# MagBase.net
KiCad netlist of a schematic drawn in EAGLE
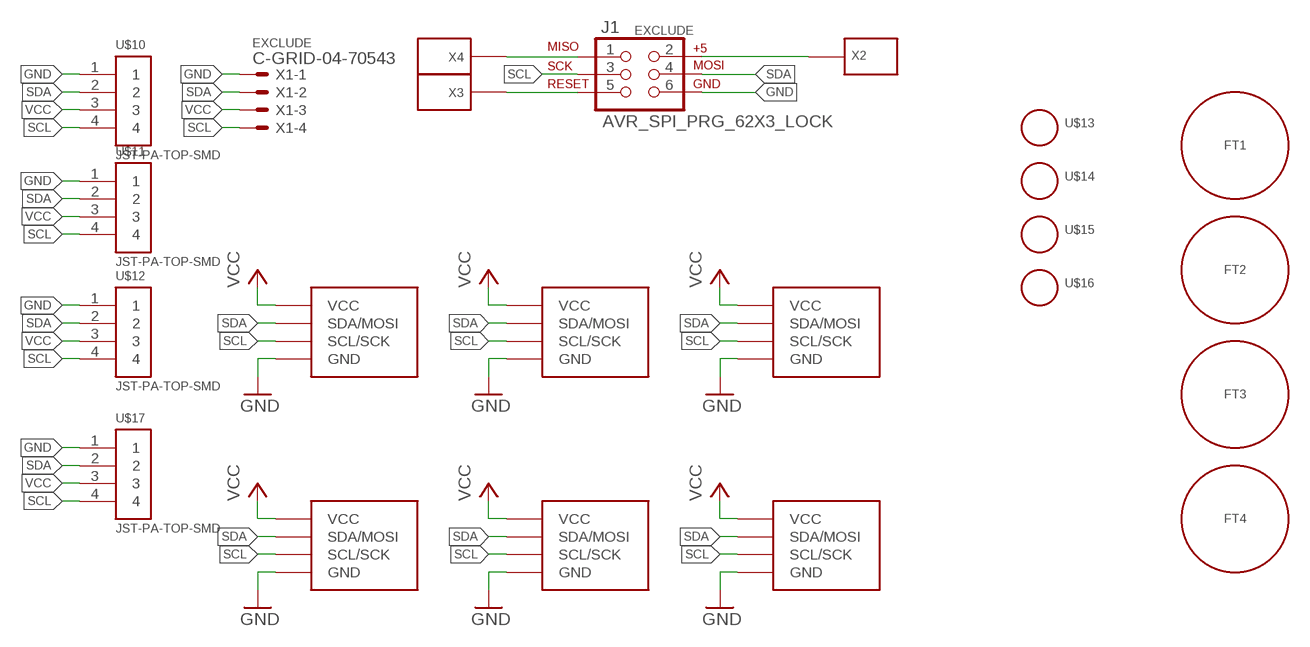
[diagram p0: schematic, sheet 1]

(export (version "E")
  (design (tool "Eeschema 10.0.6"))
  (components
    (comp (ref "FT1")
      (value "FOOT")
      (footprint "eagle-import:FOOT")
      (fields (field (name "PARTNUM") "SJ6553"))
      (libsource (lib "eagle-import") (part "FOOT"))
    )
    (comp (ref "FT2")
      (value "FOOT")
      (footprint "eagle-import:FOOT")
      (fields (field (name "PARTNUM") "SJ6553"))
      (libsource (lib "eagle-import") (part "FOOT"))
    )
    (comp (ref "FT3")
      (value "FOOT")
      (footprint "eagle-import:FOOT")
      (fields (field (name "PARTNUM") "SJ6553"))
      (libsource (lib "eagle-import") (part "FOOT"))
    )
    (comp (ref "FT4")
      (value "FOOT")
      (footprint "eagle-import:FOOT")
      (fields (field (name "PARTNUM") "SJ6553"))
      (libsource (lib "eagle-import") (part "FOOT"))
    )
    (comp (ref "J1")
      (value "AVR_SPI_PRG_62X3_LOCK")
      (footprint "eagle-import:2X3_LOCK")
      (fields (field (name "PARTNUM") "EXCLUDE"))
      (libsource (lib "eagle-import") (part "AVR_SPI_PRG_62X3_LOCK"))
    )
    (comp (ref "U$1")
      (value "MAGBASE")
      (footprint "eagle-import:MAGBASE")
      (fields (field (name "PARTNUM") "EXCLUDE"))
      (libsource (lib "eagle-import") (part "MAGBASE"))
    )
    (comp (ref "U$2")
      (value "MAGBASE")
      (footprint "eagle-import:MAGBASE")
      (fields (field (name "PARTNUM") "EXCLUDE"))
      (libsource (lib "eagle-import") (part "MAGBASE"))
    )
    (comp (ref "U$3")
      (value "MAGBASE")
      (footprint "eagle-import:MAGBASE")
      (fields (field (name "PARTNUM") "EXCLUDE"))
      (libsource (lib "eagle-import") (part "MAGBASE"))
    )
    (comp (ref "U$4")
      (value "MAGBASE")
      (footprint "eagle-import:MAGBASE")
      (fields (field (name "PARTNUM") "EXCLUDE"))
      (libsource (lib "eagle-import") (part "MAGBASE"))
    )
    (comp (ref "U$5")
      (value "MAGBASE")
      (footprint "eagle-import:MAGBASE")
      (fields (field (name "PARTNUM") "EXCLUDE"))
      (libsource (lib "eagle-import") (part "MAGBASE"))
    )
    (comp (ref "U$6")
      (value "MAGBASE")
      (footprint "eagle-import:MAGBASE")
      (fields (field (name "PARTNUM") "EXCLUDE"))
      (libsource (lib "eagle-import") (part "MAGBASE"))
    )
    (comp (ref "U$10")
      (value "JST-PA-TOP-SMD")
      (footprint "eagle-import:JST-PA-TOP-SMD")
      (fields (field (name "PARTNUM") "BM04B-PASS-1-TFT(LF)(SN)"))
      (libsource (lib "eagle-import") (part "JST-PA-TOP-SMD"))
    )
    (comp (ref "U$11")
      (value "JST-PA-TOP-SMD")
      (footprint "eagle-import:JST-PA-TOP-SMD")
      (fields (field (name "PARTNUM") "BM04B-PASS-1-TFT(LF)(SN)"))
      (libsource (lib "eagle-import") (part "JST-PA-TOP-SMD"))
    )
    (comp (ref "U$12")
      (value "JST-PA-TOP-SMD")
      (footprint "eagle-import:JST-PA-TOP-SMD")
      (fields (field (name "PARTNUM") "BM04B-PASS-1-TFT(LF)(SN)"))
      (libsource (lib "eagle-import") (part "JST-PA-TOP-SMD"))
    )
    (comp (ref "U$13")
      (value "HOLE#4")
      (footprint "eagle-import:HOLE-#4")
      (fields (field (name "PARTNUM") "EXCLUDE"))
      (libsource (lib "eagle-import") (part "HOLE#4"))
    )
    (comp (ref "U$14")
      (value "HOLE#4")
      (footprint "eagle-import:HOLE-#4")
      (fields (field (name "PARTNUM") "EXCLUDE"))
      (libsource (lib "eagle-import") (part "HOLE#4"))
    )
    (comp (ref "U$15")
      (value "HOLE#4")
      (footprint "eagle-import:HOLE-#4")
      (fields (field (name "PARTNUM") "EXCLUDE"))
      (libsource (lib "eagle-import") (part "HOLE#4"))
    )
    (comp (ref "U$16")
      (value "HOLE#4")
      (footprint "eagle-import:HOLE-#4")
      (fields (field (name "PARTNUM") "EXCLUDE"))
      (libsource (lib "eagle-import") (part "HOLE#4"))
    )
    (comp (ref "U$17")
      (value "JST-PA-TOP-SMD")
      (footprint "eagle-import:JST-PA-TOP-SMD")
      (fields (field (name "PARTNUM") "BM04B-PASS-1-TFT(LF)(SN)"))
      (libsource (lib "eagle-import") (part "JST-PA-TOP-SMD"))
    )
    (comp (ref "X1")
      (value "C-GRID-04-70543")
      (footprint "eagle-import:70543-04")
      (fields (field (name "PARTNUM") "EXCLUDE"))
      (libsource (lib "eagle-import") (part "C-GRID-04-70543"))
    )
    (comp (ref "X2")
      (value "SPRING-CONTACT")
      (footprint "eagle-import:SPRING-CONTACT")
      (fields (field (name "PARTNUM") "120220-0314"))
      (libsource (lib "eagle-import") (part "SPRING-CONTACT"))
    )
    (comp (ref "X3")
      (value "SPRING-CONTACT")
      (footprint "eagle-import:SPRING-CONTACT")
      (fields (field (name "PARTNUM") "120220-0314"))
      (libsource (lib "eagle-import") (part "SPRING-CONTACT"))
    )
    (comp (ref "X4")
      (value "SPRING-CONTACT")
      (footprint "eagle-import:SPRING-CONTACT")
      (fields (field (name "PARTNUM") "120220-0314"))
      (libsource (lib "eagle-import") (part "SPRING-CONTACT"))
    )
  )
  (nets
    (net (code "1") (name "GND") (class "Default")
      (node (ref "J1") (pin "6") (pinfunction "6_6") (pintype "passive"))
      (node (ref "U$1") (pin "GNDA") (pinfunction "GND_GNDA") (pintype "bidirectional"))
      (node (ref "U$1") (pin "GNDB") (pinfunction "GND_GNDB") (pintype "bidirectional"))
      (node (ref "U$10") (pin "1") (pinfunction "1_1") (pintype "bidirectional"))
      (node (ref "U$11") (pin "1") (pinfunction "1_1") (pintype "bidirectional"))
      (node (ref "U$12") (pin "1") (pinfunction "1_1") (pintype "bidirectional"))
      (node (ref "U$17") (pin "1") (pinfunction "1_1") (pintype "bidirectional"))
      (node (ref "U$2") (pin "GNDA") (pinfunction "GND_GNDA") (pintype "bidirectional"))
      (node (ref "U$2") (pin "GNDB") (pinfunction "GND_GNDB") (pintype "bidirectional"))
      (node (ref "U$3") (pin "GNDA") (pinfunction "GND_GNDA") (pintype "bidirectional"))
      (node (ref "U$3") (pin "GNDB") (pinfunction "GND_GNDB") (pintype "bidirectional"))
      (node (ref "U$4") (pin "GNDA") (pinfunction "GND_GNDA") (pintype "bidirectional"))
      (node (ref "U$4") (pin "GNDB") (pinfunction "GND_GNDB") (pintype "bidirectional"))
      (node (ref "U$5") (pin "GNDA") (pinfunction "GND_GNDA") (pintype "bidirectional"))
      (node (ref "U$5") (pin "GNDB") (pinfunction "GND_GNDB") (pintype "bidirectional"))
      (node (ref "U$6") (pin "GNDA") (pinfunction "GND_GNDA") (pintype "bidirectional"))
      (node (ref "U$6") (pin "GNDB") (pinfunction "GND_GNDB") (pintype "bidirectional"))
      (node (ref "X1") (pin "1") (pinfunction "S_1") (pintype "passive"))
    )
    (net (code "2") (name "Net-(J1-Pad1)") (class "Default")
      (node (ref "J1") (pin "1") (pinfunction "1_1") (pintype "passive"))
      (node (ref "X4") (pin "P$1") (pinfunction "P$1_P$1") (pintype "bidirectional"))
    )
    (net (code "3") (name "Net-(J1-Pad2)") (class "Default")
      (node (ref "J1") (pin "2") (pinfunction "2_2") (pintype "passive"))
      (node (ref "X2") (pin "P$1") (pinfunction "P$1_P$1") (pintype "bidirectional"))
    )
    (net (code "4") (name "Net-(J1-Pad5)") (class "Default")
      (node (ref "J1") (pin "5") (pinfunction "5_5") (pintype "passive"))
      (node (ref "X3") (pin "P$1") (pinfunction "P$1_P$1") (pintype "bidirectional"))
    )
    (net (code "5") (name "SCL") (class "Default")
      (node (ref "J1") (pin "3") (pinfunction "3_3") (pintype "passive"))
      (node (ref "U$1") (pin "SCLA") (pinfunction "SCL/SCK_SCLA") (pintype "bidirectional"))
      (node (ref "U$1") (pin "SCLB") (pinfunction "SCL/SCK_SCLB") (pintype "bidirectional"))
      (node (ref "U$10") (pin "4") (pinfunction "4_4") (pintype "bidirectional"))
      (node (ref "U$11") (pin "4") (pinfunction "4_4") (pintype "bidirectional"))
      (node (ref "U$12") (pin "4") (pinfunction "4_4") (pintype "bidirectional"))
      (node (ref "U$17") (pin "4") (pinfunction "4_4") (pintype "bidirectional"))
      (node (ref "U$2") (pin "SCLA") (pinfunction "SCL/SCK_SCLA") (pintype "bidirectional"))
      (node (ref "U$2") (pin "SCLB") (pinfunction "SCL/SCK_SCLB") (pintype "bidirectional"))
      (node (ref "U$3") (pin "SCLA") (pinfunction "SCL/SCK_SCLA") (pintype "bidirectional"))
      (node (ref "U$3") (pin "SCLB") (pinfunction "SCL/SCK_SCLB") (pintype "bidirectional"))
      (node (ref "U$4") (pin "SCLA") (pinfunction "SCL/SCK_SCLA") (pintype "bidirectional"))
      (node (ref "U$4") (pin "SCLB") (pinfunction "SCL/SCK_SCLB") (pintype "bidirectional"))
      (node (ref "U$5") (pin "SCLA") (pinfunction "SCL/SCK_SCLA") (pintype "bidirectional"))
      (node (ref "U$5") (pin "SCLB") (pinfunction "SCL/SCK_SCLB") (pintype "bidirectional"))
      (node (ref "U$6") (pin "SCLA") (pinfunction "SCL/SCK_SCLA") (pintype "bidirectional"))
      (node (ref "U$6") (pin "SCLB") (pinfunction "SCL/SCK_SCLB") (pintype "bidirectional"))
      (node (ref "X1") (pin "4") (pinfunction "S_4") (pintype "passive"))
    )
    (net (code "6") (name "SDA") (class "Default")
      (node (ref "J1") (pin "4") (pinfunction "4_4") (pintype "passive"))
      (node (ref "U$1") (pin "SDAA") (pinfunction "SDA/MOSI_SDAA") (pintype "bidirectional"))
      (node (ref "U$1") (pin "SDAB") (pinfunction "SDA/MOSI_SDAB") (pintype "bidirectional"))
      (node (ref "U$10") (pin "2") (pinfunction "2_2") (pintype "bidirectional"))
      (node (ref "U$11") (pin "2") (pinfunction "2_2") (pintype "bidirectional"))
      (node (ref "U$12") (pin "2") (pinfunction "2_2") (pintype "bidirectional"))
      (node (ref "U$17") (pin "2") (pinfunction "2_2") (pintype "bidirectional"))
      (node (ref "U$2") (pin "SDAA") (pinfunction "SDA/MOSI_SDAA") (pintype "bidirectional"))
      (node (ref "U$2") (pin "SDAB") (pinfunction "SDA/MOSI_SDAB") (pintype "bidirectional"))
      (node (ref "U$3") (pin "SDAA") (pinfunction "SDA/MOSI_SDAA") (pintype "bidirectional"))
      (node (ref "U$3") (pin "SDAB") (pinfunction "SDA/MOSI_SDAB") (pintype "bidirectional"))
      (node (ref "U$4") (pin "SDAA") (pinfunction "SDA/MOSI_SDAA") (pintype "bidirectional"))
      (node (ref "U$4") (pin "SDAB") (pinfunction "SDA/MOSI_SDAB") (pintype "bidirectional"))
      (node (ref "U$5") (pin "SDAA") (pinfunction "SDA/MOSI_SDAA") (pintype "bidirectional"))
      (node (ref "U$5") (pin "SDAB") (pinfunction "SDA/MOSI_SDAB") (pintype "bidirectional"))
      (node (ref "U$6") (pin "SDAA") (pinfunction "SDA/MOSI_SDAA") (pintype "bidirectional"))
      (node (ref "U$6") (pin "SDAB") (pinfunction "SDA/MOSI_SDAB") (pintype "bidirectional"))
      (node (ref "X1") (pin "2") (pinfunction "S_2") (pintype "passive"))
    )
    (net (code "7") (name "VCC") (class "Default")
      (node (ref "U$1") (pin "VCCA") (pinfunction "VCC_VCCA") (pintype "bidirectional"))
      (node (ref "U$1") (pin "VCCB") (pinfunction "VCC_VCCB") (pintype "bidirectional"))
      (node (ref "U$10") (pin "3") (pinfunction "3_3") (pintype "bidirectional"))
      (node (ref "U$11") (pin "3") (pinfunction "3_3") (pintype "bidirectional"))
      (node (ref "U$12") (pin "3") (pinfunction "3_3") (pintype "bidirectional"))
      (node (ref "U$17") (pin "3") (pinfunction "3_3") (pintype "bidirectional"))
      (node (ref "U$2") (pin "VCCA") (pinfunction "VCC_VCCA") (pintype "bidirectional"))
      (node (ref "U$2") (pin "VCCB") (pinfunction "VCC_VCCB") (pintype "bidirectional"))
      (node (ref "U$3") (pin "VCCA") (pinfunction "VCC_VCCA") (pintype "bidirectional"))
      (node (ref "U$3") (pin "VCCB") (pinfunction "VCC_VCCB") (pintype "bidirectional"))
      (node (ref "U$4") (pin "VCCA") (pinfunction "VCC_VCCA") (pintype "bidirectional"))
      (node (ref "U$4") (pin "VCCB") (pinfunction "VCC_VCCB") (pintype "bidirectional"))
      (node (ref "U$5") (pin "VCCA") (pinfunction "VCC_VCCA") (pintype "bidirectional"))
      (node (ref "U$5") (pin "VCCB") (pinfunction "VCC_VCCB") (pintype "bidirectional"))
      (node (ref "U$6") (pin "VCCA") (pinfunction "VCC_VCCA") (pintype "bidirectional"))
      (node (ref "U$6") (pin "VCCB") (pinfunction "VCC_VCCB") (pintype "bidirectional"))
      (node (ref "X1") (pin "3") (pinfunction "S_3") (pintype "passive"))
    )
    (net (code "8") (name "unconnected-(U$13-HOLE-PadP$1)") (class "Default")
      (node (ref "U$13") (pin "P$1") (pinfunction "HOLE_P$1") (pintype "bidirectional"))
    )
    (net (code "9") (name "unconnected-(U$14-HOLE-PadP$1)") (class "Default")
      (node (ref "U$14") (pin "P$1") (pinfunction "HOLE_P$1") (pintype "bidirectional"))
    )
    (net (code "10") (name "unconnected-(U$15-HOLE-PadP$1)") (class "Default")
      (node (ref "U$15") (pin "P$1") (pinfunction "HOLE_P$1") (pintype "bidirectional"))
    )
    (net (code "11") (name "unconnected-(U$16-HOLE-PadP$1)") (class "Default")
      (node (ref "U$16") (pin "P$1") (pinfunction "HOLE_P$1") (pintype "bidirectional"))
    )
  )
)
